# openThermostat_Schematic_v1.net
KiCad netlist of a schematic drawn in EAGLE
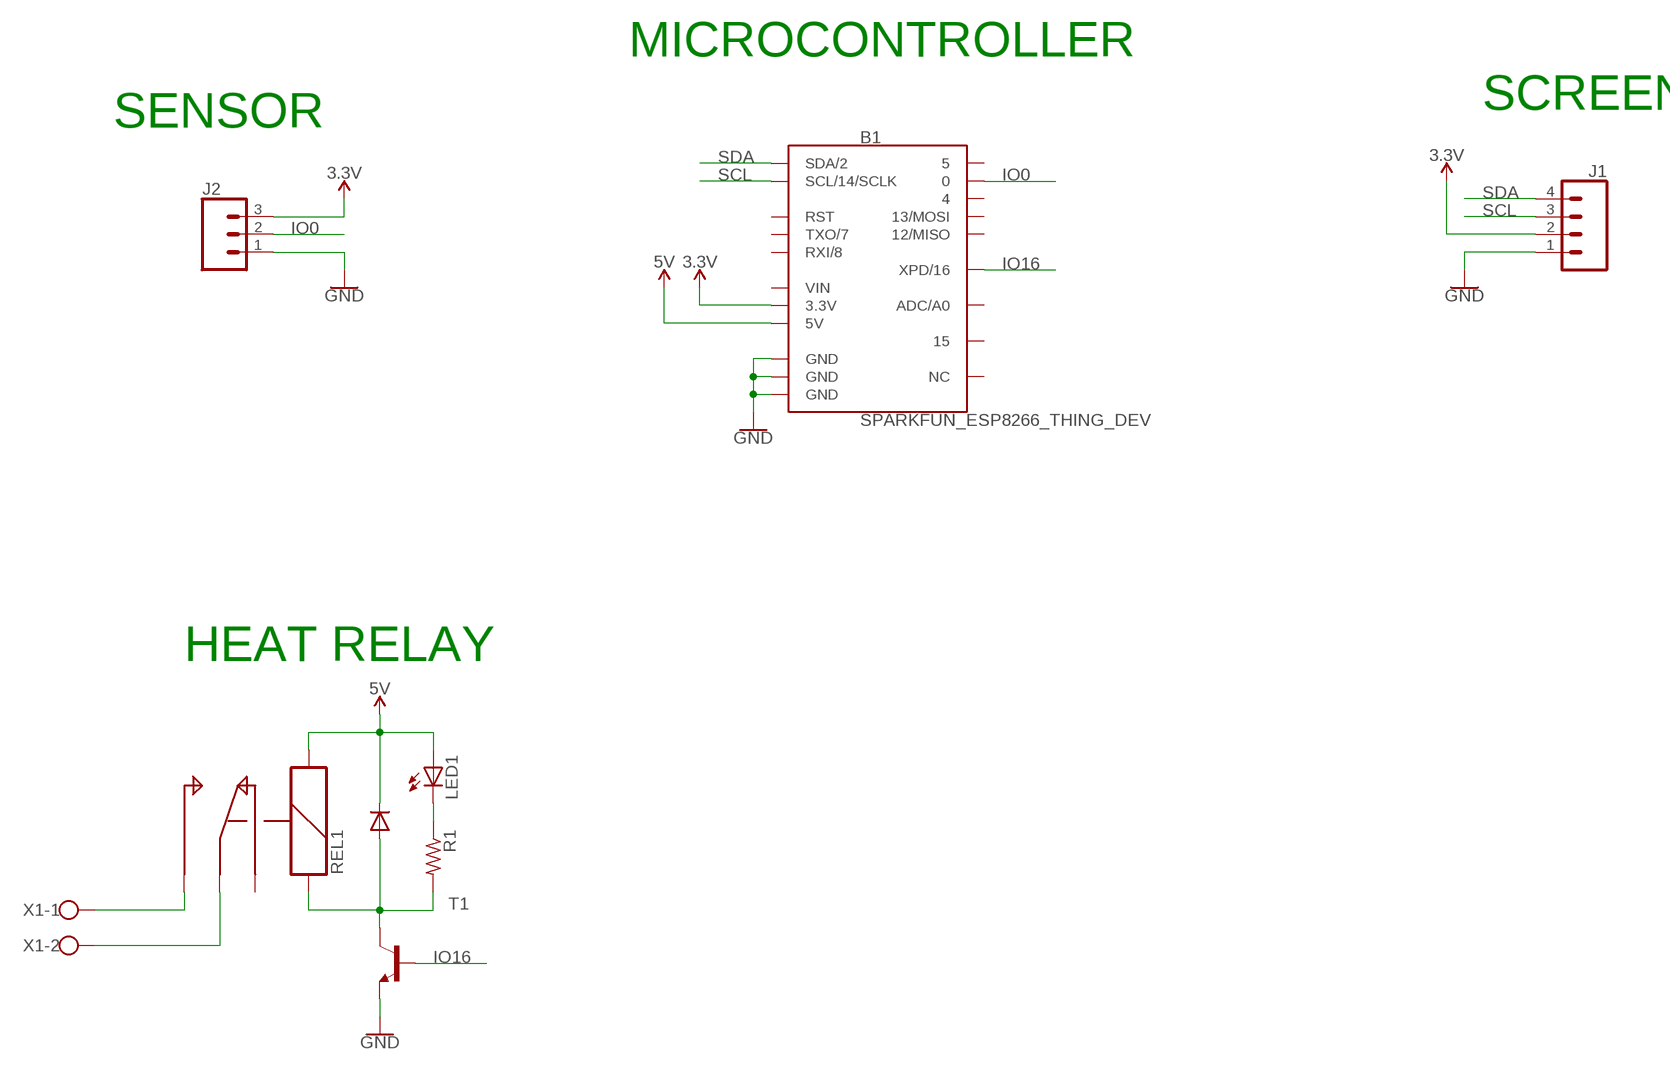
[diagram p0: schematic, sheet 1]

(export (version "E")
  (design (tool "Eeschema 10.0.6"))
  (components
    (comp (ref "B1")
      (value "SPARKFUN_ESP8266_THING_DEV")
      (footprint "eagle-import:SPARKFUN_ESP8266_THING_DEV")
      (libsource (lib "eagle-import") (part "SPARKFUN_ESP8266_THING_DEV"))
    )
    (comp (ref "J1")
      (value "CONN_04")
      (footprint "eagle-import:1X04")
      (libsource (lib "eagle-import") (part "CONN_04"))
    )
    (comp (ref "J2")
      (value "CONN_03")
      (footprint "eagle-import:1X03")
      (libsource (lib "eagle-import") (part "CONN_03"))
    )
    (comp (ref "LED1")
      (value "LED3MM")
      (footprint "eagle-import:LED3MM")
      (libsource (lib "eagle-import") (part "LED3MM"))
    )
    (comp (ref "R1")
      (value "R-US_0204/7")
      (footprint "eagle-import:0204_7")
      (libsource (lib "eagle-import") (part "R-US_0204/7"))
    )
    (comp (ref "REL1")
      (value "REL-5PIN")
      (footprint "eagle-import:REL-5PIN")
      (libsource (lib "eagle-import") (part "REL-5PIN"))
    )
    (comp (ref "T1")
      (value "2N2222-NPN-TO92-EBC")
      (footprint "eagle-import:TO92-EBC")
      (libsource (lib "eagle-import") (part "-NPN-TO92-EBC2N2222"))
    )
    (comp (ref "X1")
      (value "W237-102")
      (footprint "eagle-import:W237-102")
      (fields (field (name "MPN") "237-102"))
      (libsource (lib "eagle-import") (part "W237-102"))
    )
  )
  (nets
    (net (code "1") (name "/IO0") (class "Default")
      (node (ref "B1") (pin "0") (pinfunction "0_0") (pintype "bidirectional"))
      (node (ref "J2") (pin "2") (pinfunction "2_2") (pintype "passive"))
    )
    (net (code "2") (name "/IO16") (class "Default")
      (node (ref "B1") (pin "16") (pinfunction "XPD/16_16") (pintype "bidirectional"))
      (node (ref "T1") (pin "B") (pinfunction "B_B") (pintype "passive"))
    )
    (net (code "3") (name "/SCL") (class "Default")
      (node (ref "B1") (pin "14") (pinfunction "SCL/14/SCLK_14") (pintype "bidirectional"))
      (node (ref "J1") (pin "3") (pinfunction "3_3") (pintype "passive"))
    )
    (net (code "4") (name "/SDA") (class "Default")
      (node (ref "B1") (pin "2") (pinfunction "SDA/2_2") (pintype "bidirectional"))
      (node (ref "J1") (pin "4") (pinfunction "4_4") (pintype "passive"))
    )
    (net (code "5") (name "/VIN") (class "Default")
      (node (ref "B1") (pin "VIN") (pinfunction "VIN_VIN") (pintype "power_in"))
    )
    (net (code "6") (name "3.3V") (class "Default")
      (node (ref "B1") (pin "3.3V") (pinfunction "3.3V_3.3V") (pintype "power_in"))
      (node (ref "J1") (pin "2") (pinfunction "2_2") (pintype "passive"))
      (node (ref "J2") (pin "3") (pinfunction "3_3") (pintype "passive"))
    )
    (net (code "7") (name "5V") (class "Default")
      (node (ref "B1") (pin "5V") (pinfunction "5V_5V") (pintype "power_in"))
      (node (ref "LED1") (pin "A") (pinfunction "A_A") (pintype "passive"))
      (node (ref "REL1") (pin "S2") (pinfunction "S2_S2") (pintype "passive"))
    )
    (net (code "8") (name "GND") (class "Default")
      (node (ref "B1") (pin "GND@1") (pinfunction "GND_GND@1") (pintype "power_in"))
      (node (ref "B1") (pin "GND@2") (pinfunction "GND_GND@2") (pintype "power_in"))
      (node (ref "B1") (pin "GND@3") (pinfunction "GND_GND@3") (pintype "power_in"))
      (node (ref "J1") (pin "1") (pinfunction "1_1") (pintype "passive"))
      (node (ref "J2") (pin "1") (pinfunction "1_1") (pintype "passive"))
      (node (ref "T1") (pin "E") (pinfunction "E_E") (pintype "passive"))
    )
    (net (code "9") (name "Net-(LED1-C)") (class "Default")
      (node (ref "LED1") (pin "K") (pinfunction "C_K") (pintype "passive"))
      (node (ref "R1") (pin "1") (pinfunction "1_1") (pintype "passive"))
    )
    (net (code "10") (name "Net-(R1-Pad2)") (class "Default")
      (node (ref "R1") (pin "2") (pinfunction "2_2") (pintype "passive"))
      (node (ref "REL1") (pin "S1") (pinfunction "S1_S1") (pintype "passive"))
      (node (ref "T1") (pin "C") (pinfunction "C_C") (pintype "passive"))
    )
    (net (code "11") (name "Net-(X1A-KL)") (class "Default")
      (node (ref "REL1") (pin "O") (pinfunction "O_O") (pintype "passive"))
      (node (ref "X1") (pin "1") (pinfunction "KL_1") (pintype "passive"))
    )
    (net (code "12") (name "Net-(X1B-KL)") (class "Default")
      (node (ref "REL1") (pin "C") (pinfunction "C_C") (pintype "passive"))
      (node (ref "X1") (pin "2") (pinfunction "KL_2") (pintype "passive"))
    )
    (net (code "13") (name "unconnected-(B1-12{slash}MISO-Pad12)") (class "Default")
      (node (ref "B1") (pin "12") (pinfunction "12/MISO_12") (pintype "bidirectional"))
    )
    (net (code "14") (name "unconnected-(B1-13{slash}MOSI-Pad13)") (class "Default")
      (node (ref "B1") (pin "13") (pinfunction "13/MOSI_13") (pintype "bidirectional"))
    )
    (net (code "15") (name "unconnected-(B1-ADC{slash}A0-PadADC)") (class "Default")
      (node (ref "B1") (pin "ADC") (pinfunction "ADC/A0_ADC") (pintype "bidirectional"))
    )
    (net (code "16") (name "unconnected-(B1-Pad4)") (class "Default")
      (node (ref "B1") (pin "4") (pinfunction "4_4") (pintype "bidirectional"))
    )
    (net (code "17") (name "unconnected-(B1-Pad5)") (class "Default")
      (node (ref "B1") (pin "5") (pinfunction "5_5") (pintype "bidirectional"))
    )
    (net (code "18") (name "unconnected-(B1-Pad15)") (class "Default")
      (node (ref "B1") (pin "15") (pinfunction "15_15") (pintype "bidirectional"))
    )
    (net (code "19") (name "unconnected-(B1-PadNC)") (class "Default")
      (node (ref "B1") (pin "NC") (pinfunction "NC_NC") (pintype "no_connect"))
    )
    (net (code "20") (name "unconnected-(B1-PadRST)") (class "Default")
      (node (ref "B1") (pin "RST") (pinfunction "RST_RST") (pintype "input"))
    )
    (net (code "21") (name "unconnected-(B1-RXI{slash}8-PadRX)") (class "Default")
      (node (ref "B1") (pin "RX") (pinfunction "RXI/8_RX") (pintype "input"))
    )
    (net (code "22") (name "unconnected-(B1-TXO{slash}7-PadTX)") (class "Default")
      (node (ref "B1") (pin "TX") (pinfunction "TXO/7_TX") (pintype "output"))
    )
    (net (code "23") (name "unconnected-(REL1-PadS)") (class "Default")
      (node (ref "REL1") (pin "S") (pinfunction "S_S") (pintype "passive"))
    )
  )
)
